# P1_CCD_CAM_BOARD_OVERVIEW.net
KiCad netlist of a schematic drawn in Altium Designer
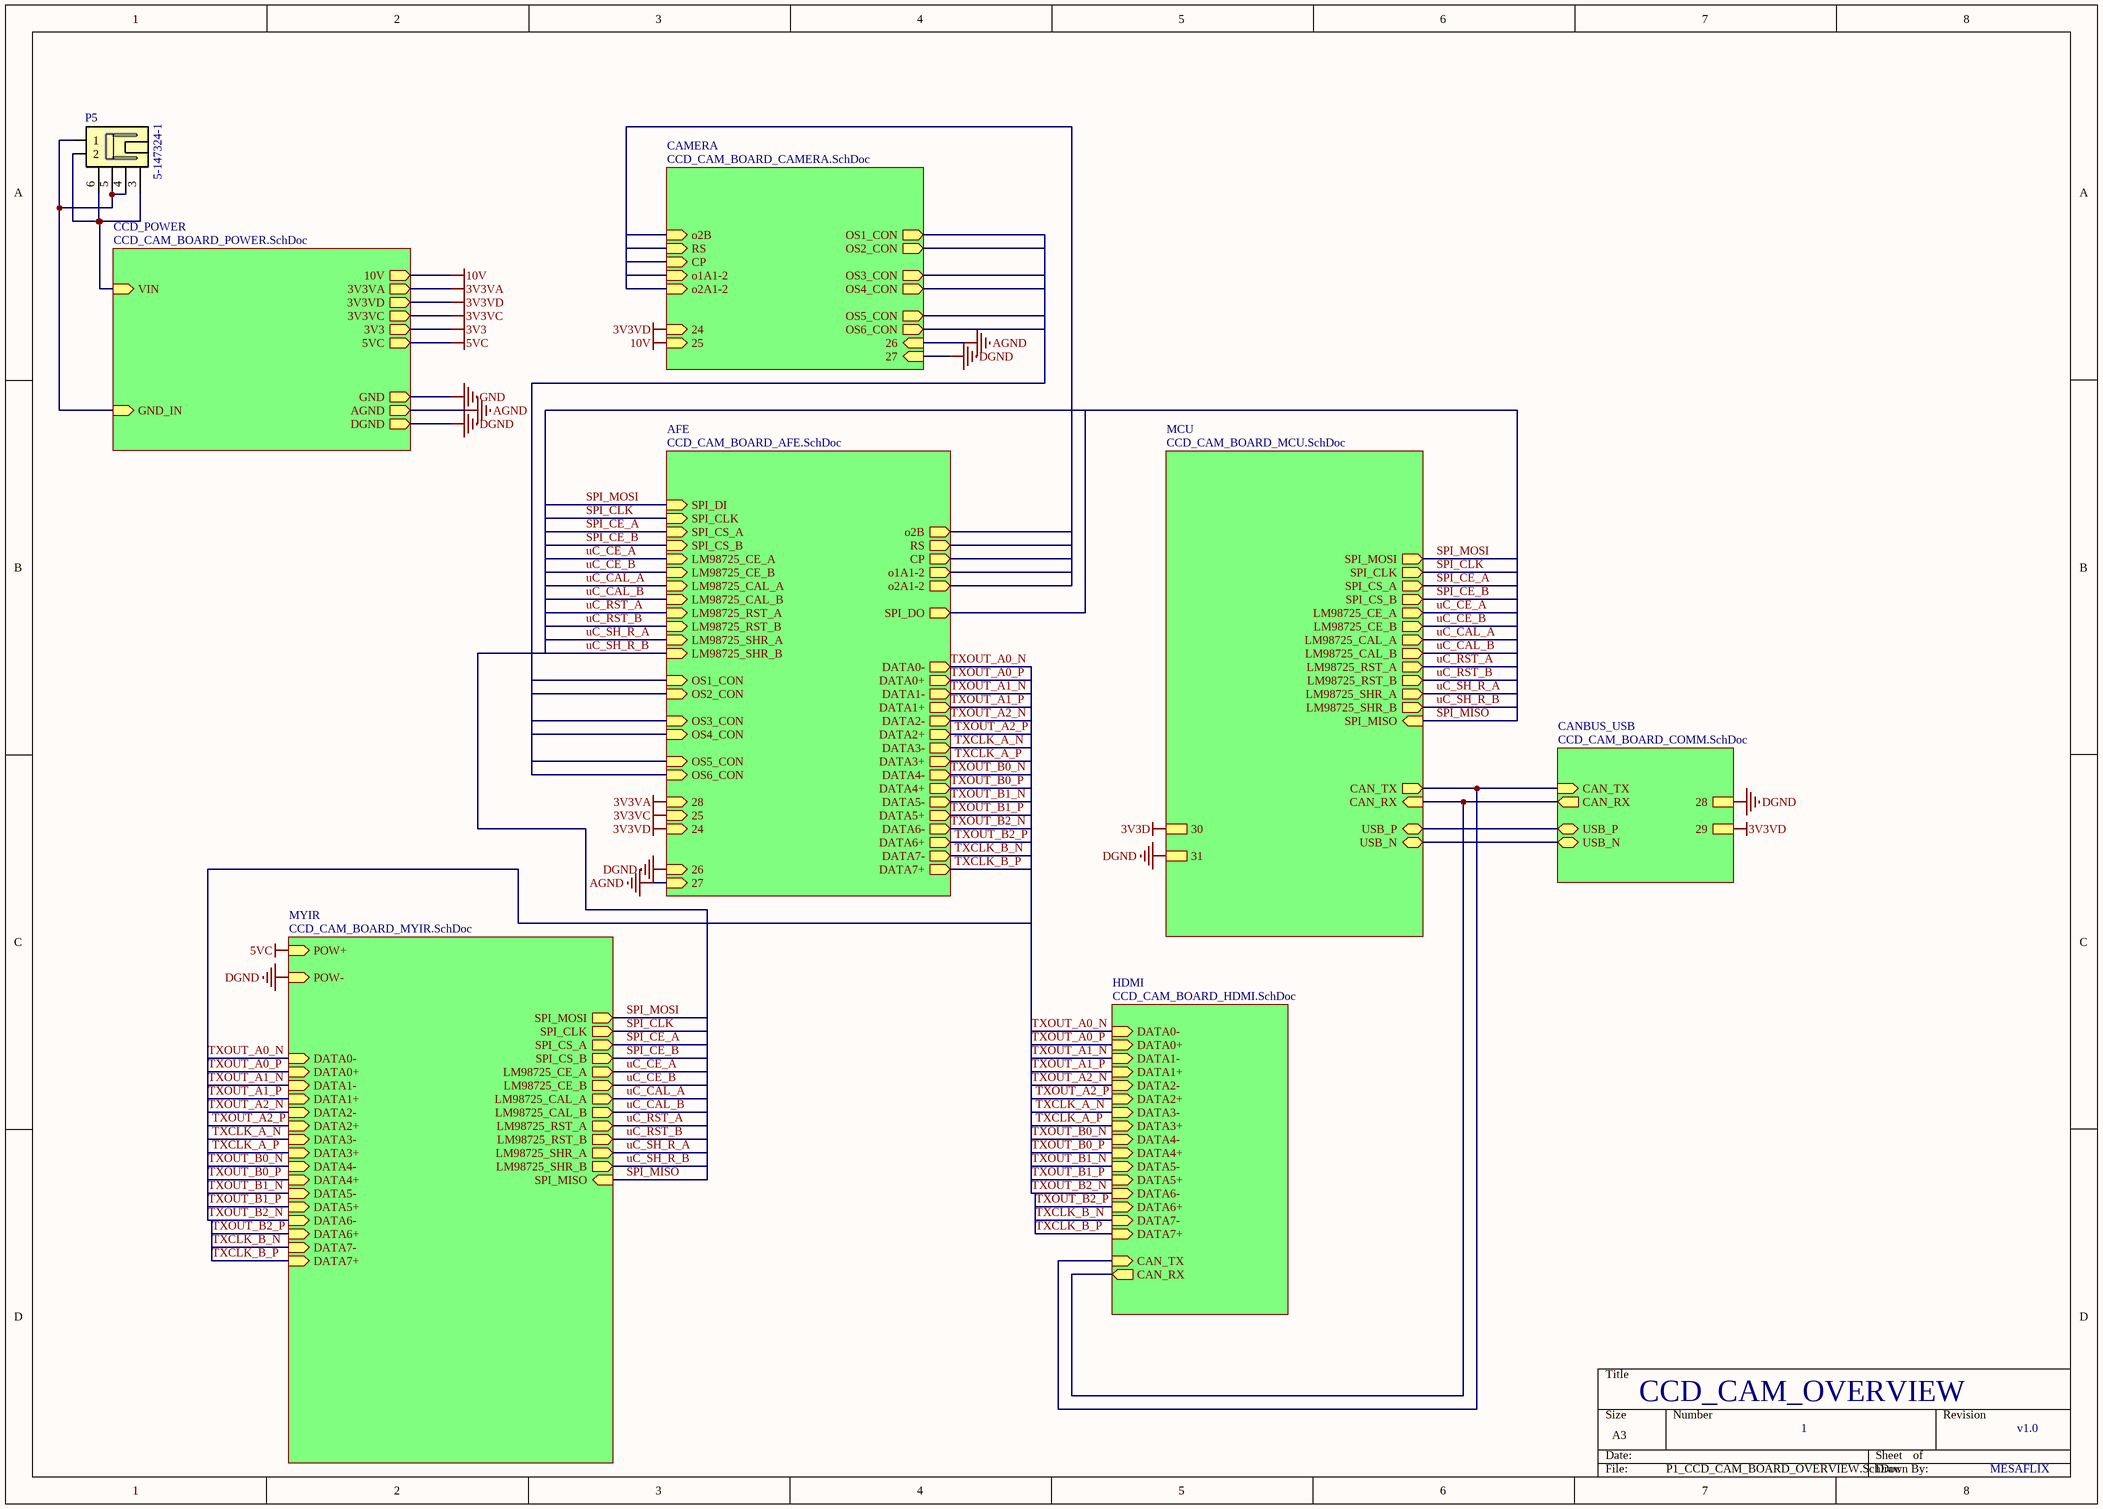
[diagram p0: P1_CCD_CAM_BOARD_OVERVIEW.SchDoc]

(export (version "E")
  (design (tool "Eeschema 10.0.6"))
  (components
    (comp (ref "P5")
      (value "5-147324-1")
      (footprint "TE_5-147324-1")
      (description "HEADER SMD R/A 2POS 2.54MM")
      (fields (field (name "PUBLISHER") "Altium Limited"))
      (libsource (lib "CCD_board") (part "SMDHDR1x2-RA"))
    )
  )
  (nets
    (net (code "5") (name "/GND_IN") (class "Default")
      (node (ref "P5") (pin "1") (pinfunction "1_1") (pintype "passive"))
      (node (ref "P5") (pin "4") (pinfunction "SHIELD_4") (pintype "passive"))
      (node (ref "P5") (pin "5") (pinfunction "SHIELD_5") (pintype "passive"))
    )
    (net (code "30") (name "/VIN") (class "Default")
      (node (ref "P5") (pin "2") (pinfunction "2_2") (pintype "passive"))
      (node (ref "P5") (pin "3") (pinfunction "SHIELD_3") (pintype "passive"))
      (node (ref "P5") (pin "6") (pinfunction "SHIELD_6") (pintype "passive"))
    )
  )
)
